# design.net
KiCad netlist of a schematic drawn in EasyEDA Pro
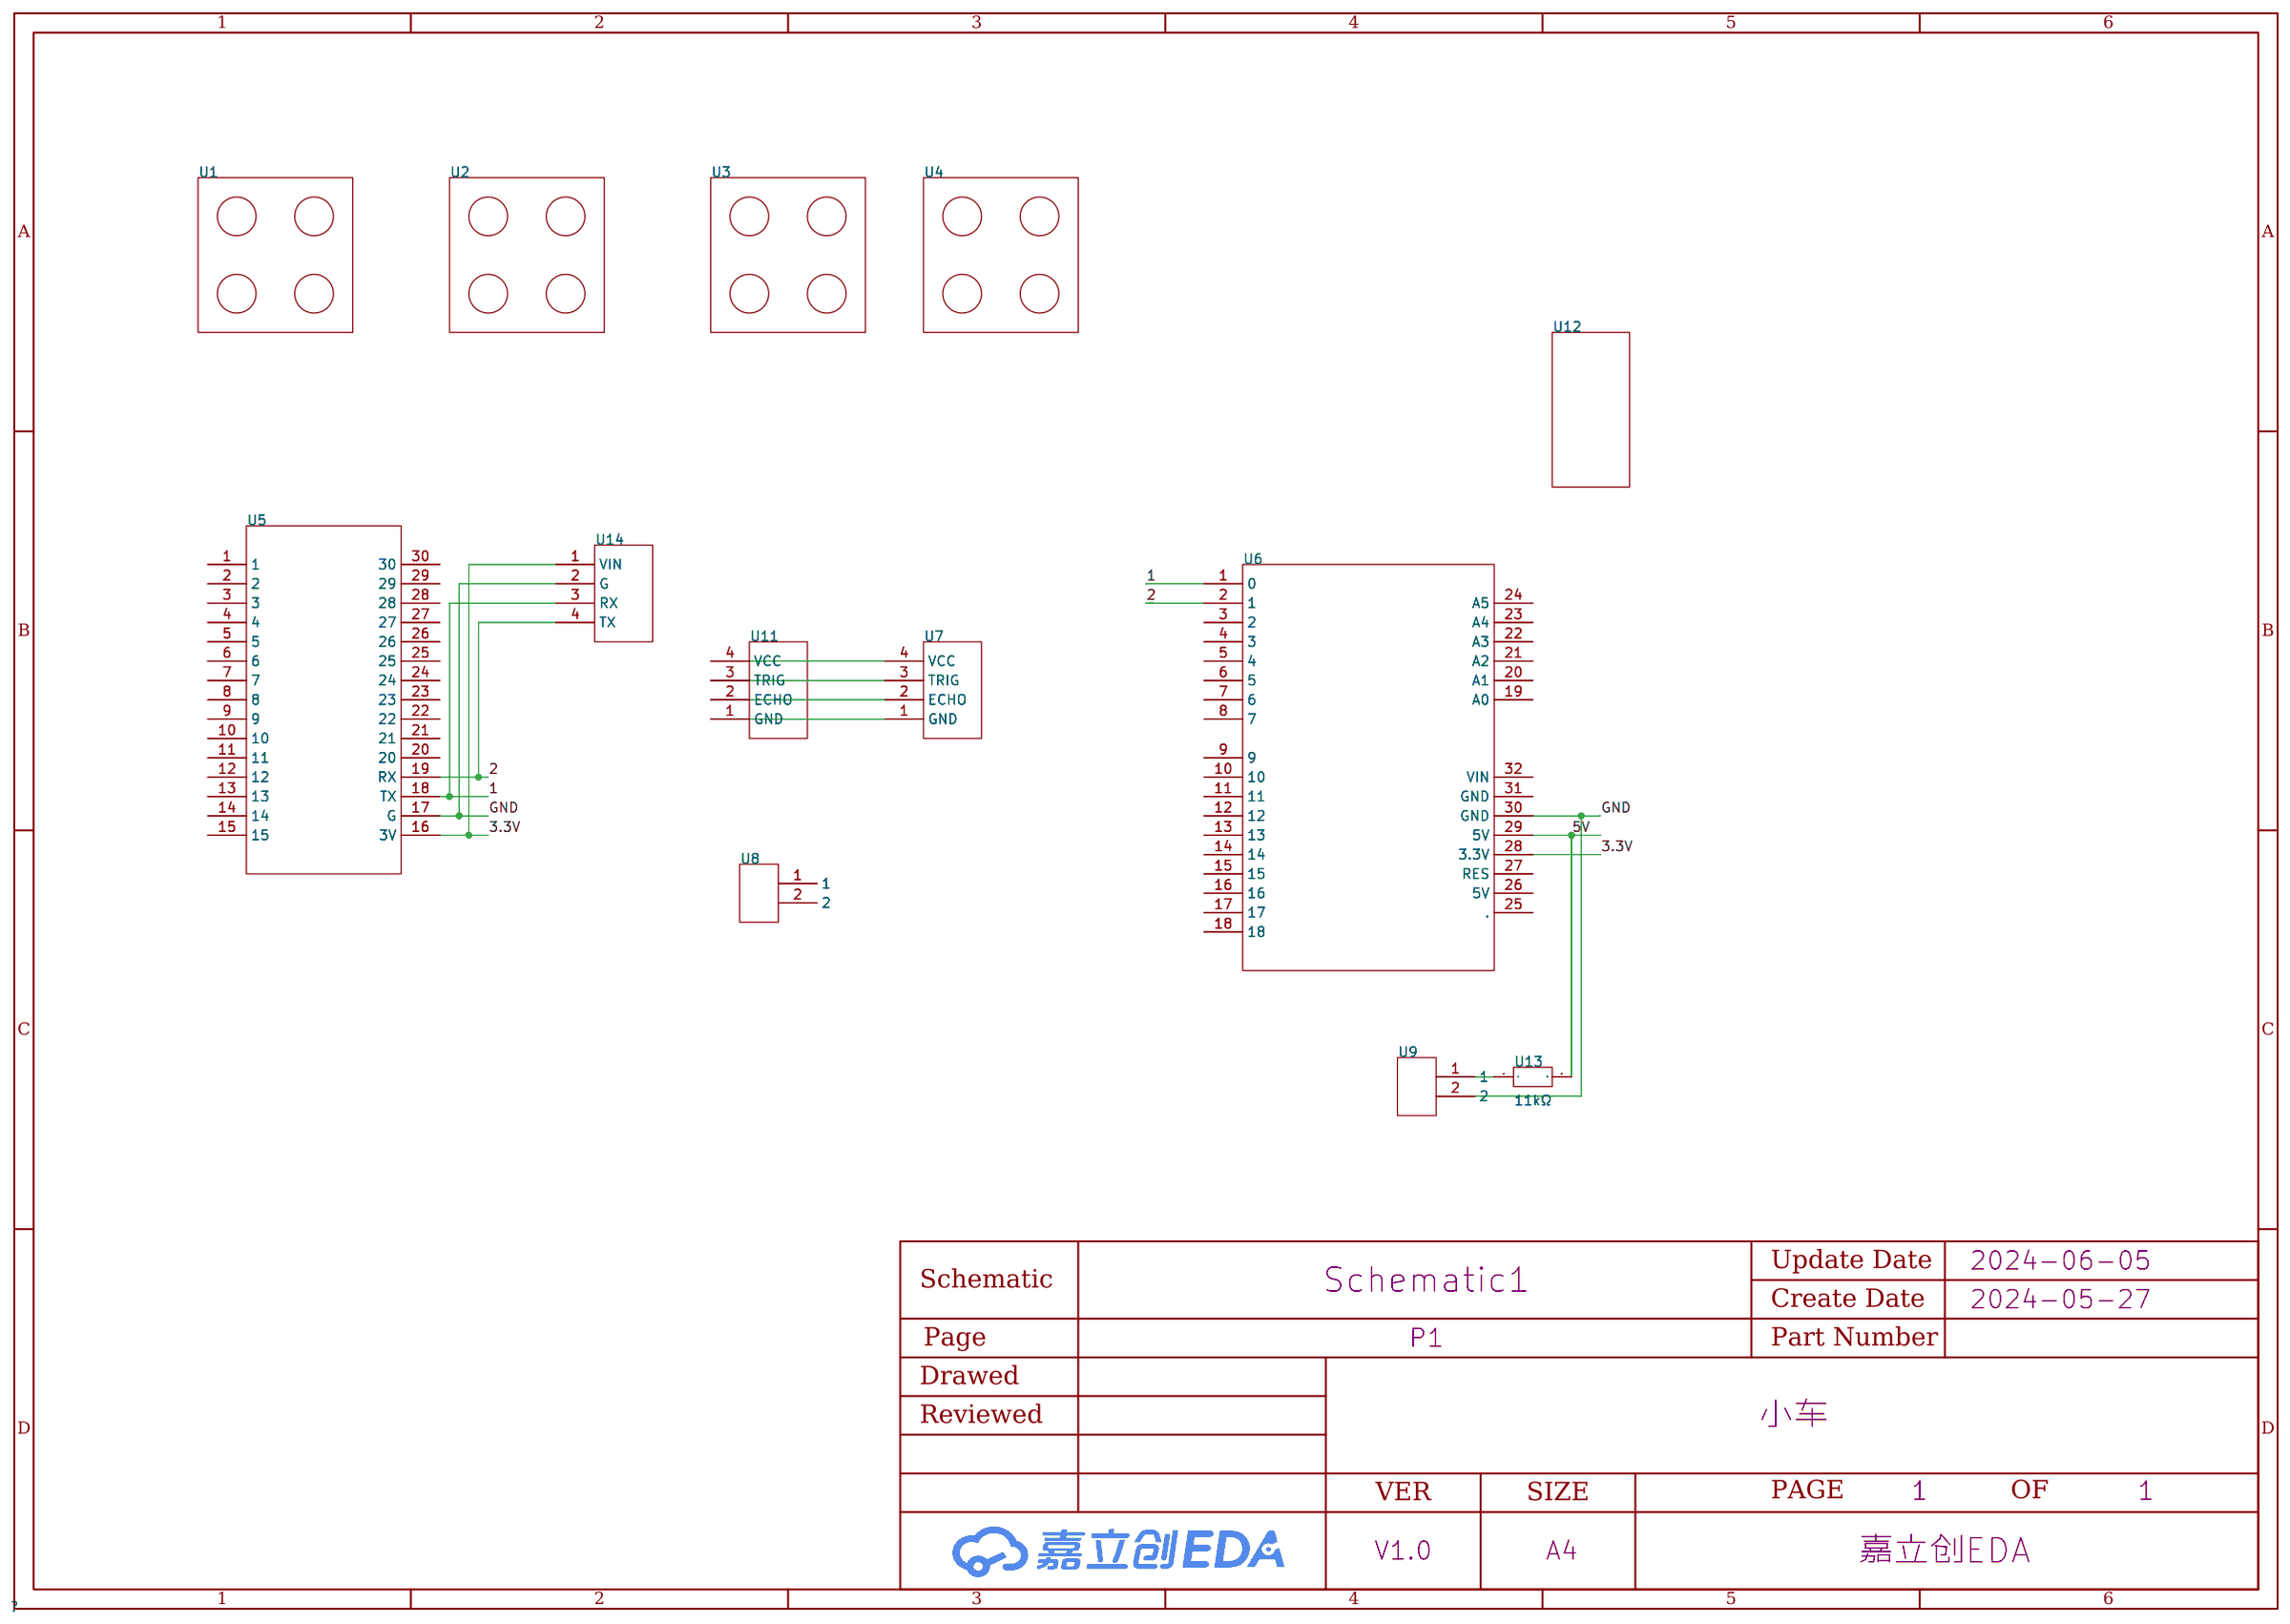
[diagram p0: schematic sheet]

(export (version "E")
  (design (tool "Eeschema 10.0.6"))
  (components
    (comp (ref "U1") (value "~") (footprint "easyedapro:车轮") (libsource (lib "easyedapro") (part "车轮")))
    (comp (ref "U2") (value "~") (footprint "easyedapro:车轮") (libsource (lib "easyedapro") (part "车轮")))
    (comp (ref "U3") (value "~") (footprint "easyedapro:车轮") (libsource (lib "easyedapro") (part "车轮")))
    (comp (ref "U4") (value "~") (footprint "easyedapro:车轮") (libsource (lib "easyedapro") (part "车轮")))
    (comp (ref "U5") (value "~") (footprint "easyedapro:蓝牙") (libsource (lib "easyedapro") (part "蓝牙")))
    (comp (ref "U6") (value "~") (footprint "easyedapro:开发板") (libsource (lib "easyedapro") (part "开发板")))
    (comp (ref "U7") (value "~") (footprint "easyedapro:雷达") (libsource (lib "easyedapro") (part "雷达")))
    (comp (ref "U8") (value "~") (footprint "easyedapro:开关") (libsource (lib "easyedapro") (part "开关")))
    (comp (ref "U9") (value "~") (footprint "easyedapro:开关") (libsource (lib "easyedapro") (part "开关")))
    (comp (ref "U11") (value "~") (footprint "easyedapro:雷达") (libsource (lib "easyedapro") (part "雷达")))
    (comp (ref "U12") (value "~") (footprint "easyedapro:舵机") (libsource (lib "easyedapro") (part "舵机")))
    (comp (ref "U13")
      (value "11kΩ")
      (footprint "easyedapro:RES-TH_BD2.3-L6.0-P10.00-D0.6")
      (description "电阻类型:金属膜电阻;阻值:11kΩ;精度:±1%;功率:125mW;温度系数:±100ppm/°C;")
      (fields (field (name "Manufacturer Part") "RN55D1102FB14") (field (name "Manufacturer") "VISHAY(威世)"))
      (libsource (lib "easyedapro") (part "RN55D1102FB14"))
    )
    (comp (ref "U14")
      (value "~")
      (footprint "easyedapro:OPENMV")
      (libsource (lib "easyedapro") (part "opnemv"))
    )
  )
  (nets
    (net (code "1") (name "/1") (class "Default")
      (node (ref "U14") (pin "3") (pinfunction "RX_3") (pintype "input"))
      (node (ref "U5") (pin "18") (pinfunction "TX_18") (pintype "input"))
      (node (ref "U6") (pin "1") (pinfunction "0_1") (pintype "input"))
    )
    (net (code "2") (name "/2") (class "Default")
      (node (ref "U14") (pin "4") (pinfunction "TX_4") (pintype "input"))
      (node (ref "U5") (pin "19") (pinfunction "RX_19") (pintype "input"))
      (node (ref "U6") (pin "2") (pinfunction "1_2") (pintype "input"))
    )
    (net (code "3") (name "/3.3V") (class "Default")
      (node (ref "U14") (pin "1") (pinfunction "VIN_1") (pintype "input"))
      (node (ref "U5") (pin "16") (pinfunction "3V_16") (pintype "input"))
      (node (ref "U6") (pin "28") (pinfunction "3.3V_28") (pintype "input"))
    )
    (net (code "4") (name "/5V") (class "Default")
      (node (ref "U13") (pin "2") (pinfunction "2_2") (pintype "unspecified"))
      (node (ref "U6") (pin "29") (pinfunction "5V_29") (pintype "input"))
    )
    (net (code "5") (name "/GND") (class "Default")
      (node (ref "U14") (pin "2") (pinfunction "G_2") (pintype "input"))
      (node (ref "U5") (pin "17") (pinfunction "G_17") (pintype "input"))
      (node (ref "U6") (pin "30") (pinfunction "GND_30") (pintype "input"))
      (node (ref "U9") (pin "2") (pinfunction "2_2") (pintype "input"))
    )
    (net (code "6") (name "Net-(U11-ECHO)") (class "Default")
      (node (ref "U11") (pin "2") (pinfunction "ECHO_2") (pintype "input"))
      (node (ref "U7") (pin "2") (pinfunction "ECHO_2") (pintype "input"))
    )
    (net (code "7") (name "Net-(U11-GND)") (class "Default")
      (node (ref "U11") (pin "1") (pinfunction "GND_1") (pintype "input"))
      (node (ref "U7") (pin "1") (pinfunction "GND_1") (pintype "input"))
    )
    (net (code "8") (name "Net-(U11-TRIG)") (class "Default")
      (node (ref "U11") (pin "3") (pinfunction "TRIG_3") (pintype "input"))
      (node (ref "U7") (pin "3") (pinfunction "TRIG_3") (pintype "input"))
    )
    (net (code "9") (name "Net-(U11-VCC)") (class "Default")
      (node (ref "U11") (pin "4") (pinfunction "VCC_4") (pintype "input"))
      (node (ref "U7") (pin "4") (pinfunction "VCC_4") (pintype "input"))
    )
    (net (code "10") (name "Net-(U13-Pad1)") (class "Default")
      (node (ref "U13") (pin "1") (pinfunction "1_1") (pintype "unspecified"))
      (node (ref "U9") (pin "1") (pinfunction "1_1") (pintype "input"))
    )
    (net (code "11") (name "unconnected-(U5-Pad1)") (class "Default")
      (node (ref "U5") (pin "1") (pinfunction "1_1") (pintype "input"))
    )
    (net (code "12") (name "unconnected-(U5-Pad2)") (class "Default")
      (node (ref "U5") (pin "2") (pinfunction "2_2") (pintype "input"))
    )
    (net (code "13") (name "unconnected-(U5-Pad3)") (class "Default")
      (node (ref "U5") (pin "3") (pinfunction "3_3") (pintype "input"))
    )
    (net (code "14") (name "unconnected-(U5-Pad4)") (class "Default")
      (node (ref "U5") (pin "4") (pinfunction "4_4") (pintype "input"))
    )
    (net (code "15") (name "unconnected-(U5-Pad5)") (class "Default")
      (node (ref "U5") (pin "5") (pinfunction "5_5") (pintype "input"))
    )
    (net (code "16") (name "unconnected-(U5-Pad6)") (class "Default")
      (node (ref "U5") (pin "6") (pinfunction "6_6") (pintype "input"))
    )
    (net (code "17") (name "unconnected-(U5-Pad7)") (class "Default")
      (node (ref "U5") (pin "7") (pinfunction "7_7") (pintype "input"))
    )
    (net (code "18") (name "unconnected-(U5-Pad8)") (class "Default")
      (node (ref "U5") (pin "8") (pinfunction "8_8") (pintype "input"))
    )
    (net (code "19") (name "unconnected-(U5-Pad9)") (class "Default")
      (node (ref "U5") (pin "9") (pinfunction "9_9") (pintype "input"))
    )
    (net (code "20") (name "unconnected-(U5-Pad10)") (class "Default")
      (node (ref "U5") (pin "10") (pinfunction "10_10") (pintype "input"))
    )
    (net (code "21") (name "unconnected-(U5-Pad11)") (class "Default")
      (node (ref "U5") (pin "11") (pinfunction "11_11") (pintype "input"))
    )
    (net (code "22") (name "unconnected-(U5-Pad12)") (class "Default")
      (node (ref "U5") (pin "12") (pinfunction "12_12") (pintype "input"))
    )
    (net (code "23") (name "unconnected-(U5-Pad13)") (class "Default")
      (node (ref "U5") (pin "13") (pinfunction "13_13") (pintype "input"))
    )
    (net (code "24") (name "unconnected-(U5-Pad14)") (class "Default")
      (node (ref "U5") (pin "14") (pinfunction "14_14") (pintype "input"))
    )
    (net (code "25") (name "unconnected-(U5-Pad15)") (class "Default")
      (node (ref "U5") (pin "15") (pinfunction "15_15") (pintype "input"))
    )
    (net (code "26") (name "unconnected-(U5-Pad20)") (class "Default")
      (node (ref "U5") (pin "20") (pinfunction "20_20") (pintype "input"))
    )
    (net (code "27") (name "unconnected-(U5-Pad21)") (class "Default")
      (node (ref "U5") (pin "21") (pinfunction "21_21") (pintype "input"))
    )
    (net (code "28") (name "unconnected-(U5-Pad22)") (class "Default")
      (node (ref "U5") (pin "22") (pinfunction "22_22") (pintype "input"))
    )
    (net (code "29") (name "unconnected-(U5-Pad23)") (class "Default")
      (node (ref "U5") (pin "23") (pinfunction "23_23") (pintype "input"))
    )
    (net (code "30") (name "unconnected-(U5-Pad24)") (class "Default")
      (node (ref "U5") (pin "24") (pinfunction "24_24") (pintype "input"))
    )
    (net (code "31") (name "unconnected-(U5-Pad25)") (class "Default")
      (node (ref "U5") (pin "25") (pinfunction "25_25") (pintype "input"))
    )
    (net (code "32") (name "unconnected-(U5-Pad26)") (class "Default")
      (node (ref "U5") (pin "26") (pinfunction "26_26") (pintype "input"))
    )
    (net (code "33") (name "unconnected-(U5-Pad27)") (class "Default")
      (node (ref "U5") (pin "27") (pinfunction "27_27") (pintype "input"))
    )
    (net (code "34") (name "unconnected-(U5-Pad28)") (class "Default")
      (node (ref "U5") (pin "28") (pinfunction "28_28") (pintype "input"))
    )
    (net (code "35") (name "unconnected-(U5-Pad29)") (class "Default")
      (node (ref "U5") (pin "29") (pinfunction "29_29") (pintype "input"))
    )
    (net (code "36") (name "unconnected-(U5-Pad30)") (class "Default")
      (node (ref "U5") (pin "30") (pinfunction "30_30") (pintype "input"))
    )
    (net (code "37") (name "unconnected-(U6-.-Pad25)") (class "Default")
      (node (ref "U6") (pin "25") (pinfunction "._25") (pintype "input"))
    )
    (net (code "38") (name "unconnected-(U6-2-Pad3)") (class "Default")
      (node (ref "U6") (pin "3") (pinfunction "2_3") (pintype "input"))
    )
    (net (code "39") (name "unconnected-(U6-3-Pad4)") (class "Default")
      (node (ref "U6") (pin "4") (pinfunction "3_4") (pintype "input"))
    )
    (net (code "40") (name "unconnected-(U6-4-Pad5)") (class "Default")
      (node (ref "U6") (pin "5") (pinfunction "4_5") (pintype "input"))
    )
    (net (code "41") (name "unconnected-(U6-5-Pad6)") (class "Default")
      (node (ref "U6") (pin "6") (pinfunction "5_6") (pintype "input"))
    )
    (net (code "42") (name "unconnected-(U6-5V-Pad26)") (class "Default")
      (node (ref "U6") (pin "26") (pinfunction "5V_26") (pintype "input"))
    )
    (net (code "43") (name "unconnected-(U6-6-Pad7)") (class "Default")
      (node (ref "U6") (pin "7") (pinfunction "6_7") (pintype "input"))
    )
    (net (code "44") (name "unconnected-(U6-7-Pad8)") (class "Default")
      (node (ref "U6") (pin "8") (pinfunction "7_8") (pintype "input"))
    )
    (net (code "45") (name "unconnected-(U6-A0-Pad19)") (class "Default")
      (node (ref "U6") (pin "19") (pinfunction "A0_19") (pintype "input"))
    )
    (net (code "46") (name "unconnected-(U6-A1-Pad20)") (class "Default")
      (node (ref "U6") (pin "20") (pinfunction "A1_20") (pintype "input"))
    )
    (net (code "47") (name "unconnected-(U6-A2-Pad21)") (class "Default")
      (node (ref "U6") (pin "21") (pinfunction "A2_21") (pintype "input"))
    )
    (net (code "48") (name "unconnected-(U6-A3-Pad22)") (class "Default")
      (node (ref "U6") (pin "22") (pinfunction "A3_22") (pintype "input"))
    )
    (net (code "49") (name "unconnected-(U6-A4-Pad23)") (class "Default")
      (node (ref "U6") (pin "23") (pinfunction "A4_23") (pintype "input"))
    )
    (net (code "50") (name "unconnected-(U6-A5-Pad24)") (class "Default")
      (node (ref "U6") (pin "24") (pinfunction "A5_24") (pintype "input"))
    )
    (net (code "51") (name "unconnected-(U6-GND-Pad31)") (class "Default")
      (node (ref "U6") (pin "31") (pinfunction "GND_31") (pintype "input"))
    )
    (net (code "52") (name "unconnected-(U6-Pad9)") (class "Default")
      (node (ref "U6") (pin "9") (pinfunction "9_9") (pintype "input"))
    )
    (net (code "53") (name "unconnected-(U6-Pad10)") (class "Default")
      (node (ref "U6") (pin "10") (pinfunction "10_10") (pintype "input"))
    )
    (net (code "54") (name "unconnected-(U6-Pad11)") (class "Default")
      (node (ref "U6") (pin "11") (pinfunction "11_11") (pintype "input"))
    )
    (net (code "55") (name "unconnected-(U6-Pad12)") (class "Default")
      (node (ref "U6") (pin "12") (pinfunction "12_12") (pintype "input"))
    )
    (net (code "56") (name "unconnected-(U6-Pad13)") (class "Default")
      (node (ref "U6") (pin "13") (pinfunction "13_13") (pintype "input"))
    )
    (net (code "57") (name "unconnected-(U6-Pad14)") (class "Default")
      (node (ref "U6") (pin "14") (pinfunction "14_14") (pintype "input"))
    )
    (net (code "58") (name "unconnected-(U6-Pad15)") (class "Default")
      (node (ref "U6") (pin "15") (pinfunction "15_15") (pintype "input"))
    )
    (net (code "59") (name "unconnected-(U6-Pad16)") (class "Default")
      (node (ref "U6") (pin "16") (pinfunction "16_16") (pintype "input"))
    )
    (net (code "60") (name "unconnected-(U6-Pad17)") (class "Default")
      (node (ref "U6") (pin "17") (pinfunction "17_17") (pintype "input"))
    )
    (net (code "61") (name "unconnected-(U6-Pad18)") (class "Default")
      (node (ref "U6") (pin "18") (pinfunction "18_18") (pintype "input"))
    )
    (net (code "62") (name "unconnected-(U6-RES-Pad27)") (class "Default")
      (node (ref "U6") (pin "27") (pinfunction "RES_27") (pintype "input"))
    )
    (net (code "63") (name "unconnected-(U6-VIN-Pad32)") (class "Default")
      (node (ref "U6") (pin "32") (pinfunction "VIN_32") (pintype "input"))
    )
    (net (code "64") (name "unconnected-(U8-Pad1)") (class "Default")
      (node (ref "U8") (pin "1") (pinfunction "1_1") (pintype "input"))
    )
    (net (code "65") (name "unconnected-(U8-Pad2)") (class "Default")
      (node (ref "U8") (pin "2") (pinfunction "2_2") (pintype "input"))
    )
  )
)
